# RF_circuit.net
KiCad netlist of a schematic drawn in Altium Designer
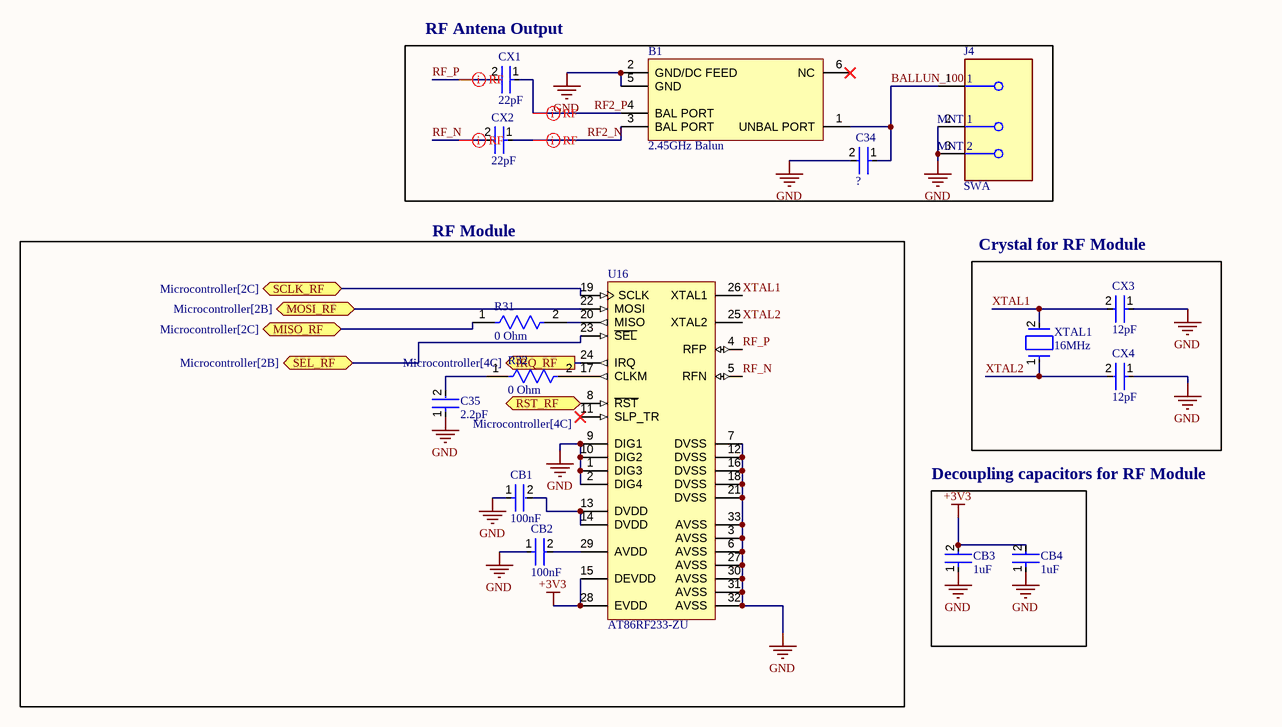
[diagram p0: RF_circuit.SchDoc]

(export (version "E")
  (design (tool "Eeschema 10.0.6"))
  (components
    (comp (ref "B1")
      (value "2.45GHz Balun")
      (footprint "WE-BAL_0805")
      (description "748421245 100O Surface Mount Chip Balun")
      (libsource (lib "Altium Content Vault") (part "WE-BAL_0805"))
    )
    (comp (ref "C34")
      (value "?")
      (footprint "FP-CC0805-0_85-MFG")
      (description "CAP CER 0.1UF 50V X7R 0805")
      (fields (field (name "TOLERANCE") "0.1") (field (name "MANUFACTURER PART NUMBER") "CC0805KRX7R9BB104"))
      (libsource (lib "Altium Content Vault") (part "11868f565c42a9108669ba33697ecf6"))
    )
    (comp (ref "C35")
      (value "2.2pF")
      (footprint "FP-CC0805-0_85-MFG")
      (description "CAP CER 0.1UF 50V X7R 0805")
      (fields (field (name "TOLERANCE") "0.1") (field (name "MANUFACTURER PART NUMBER") "CC0805KRX7R9BB104"))
      (libsource (lib "Altium Content Vault") (part "11868f565c42a9108669ba33697ecf6"))
    )
    (comp (ref "CB1")
      (value "100nF")
      (footprint "FP-CC0805-0_85-MFG")
      (description "CAP CER 0.1UF 50V X7R 0805")
      (fields (field (name "TOLERANCE") "0.1") (field (name "MANUFACTURER PART NUMBER") "CC0805KRX7R9BB104"))
      (libsource (lib "Altium Content Vault") (part "11868f565c42a9108669ba33697ecf6"))
    )
    (comp (ref "CB2")
      (value "100nF")
      (footprint "FP-CC0805-0_85-MFG")
      (description "CAP CER 0.1UF 50V X7R 0805")
      (fields (field (name "TOLERANCE") "0.1") (field (name "MANUFACTURER PART NUMBER") "CC0805KRX7R9BB104"))
      (libsource (lib "Altium Content Vault") (part "11868f565c42a9108669ba33697ecf6"))
    )
    (comp (ref "CB3")
      (value "1uF")
      (footprint "FP-CC0805-0_85-MFG")
      (description "CAP CER 0.1UF 50V X7R 0805")
      (fields (field (name "TOLERANCE") "0.1") (field (name "MANUFACTURER PART NUMBER") "CC0805KRX7R9BB104"))
      (libsource (lib "Altium Content Vault") (part "11868f565c42a9108669ba33697ecf6"))
    )
    (comp (ref "CB4")
      (value "1uF")
      (footprint "FP-CC0805-0_85-MFG")
      (description "CAP CER 0.1UF 50V X7R 0805")
      (fields (field (name "TOLERANCE") "0.1") (field (name "MANUFACTURER PART NUMBER") "CC0805KRX7R9BB104"))
      (libsource (lib "Altium Content Vault") (part "11868f565c42a9108669ba33697ecf6"))
    )
    (comp (ref "CX1")
      (value "22pF")
      (footprint "FP-CC0805-0_85-MFG")
      (description "CAP CER 0.1UF 50V X7R 0805")
      (fields (field (name "TOLERANCE") "0.1") (field (name "MANUFACTURER PART NUMBER") "CC0805KRX7R9BB104"))
      (libsource (lib "Altium Content Vault") (part "11868f565c42a9108669ba33697ecf6"))
    )
    (comp (ref "CX2")
      (value "22pF")
      (footprint "FP-CC0805-0_85-MFG")
      (description "CAP CER 0.1UF 50V X7R 0805")
      (fields (field (name "TOLERANCE") "0.1") (field (name "MANUFACTURER PART NUMBER") "CC0805KRX7R9BB104"))
      (libsource (lib "Altium Content Vault") (part "11868f565c42a9108669ba33697ecf6"))
    )
    (comp (ref "CX3")
      (value "12pF")
      (footprint "FP-CC0805-0_85-MFG")
      (description "CAP CER 0.1UF 50V X7R 0805")
      (fields (field (name "TOLERANCE") "0.1") (field (name "MANUFACTURER PART NUMBER") "CC0805KRX7R9BB104"))
      (libsource (lib "Altium Content Vault") (part "11868f565c42a9108669ba33697ecf6"))
    )
    (comp (ref "CX4")
      (value "12pF")
      (footprint "FP-CC0805-0_85-MFG")
      (description "CAP CER 0.1UF 50V X7R 0805")
      (fields (field (name "TOLERANCE") "0.1") (field (name "MANUFACTURER PART NUMBER") "CC0805KRX7R9BB104"))
      (libsource (lib "Altium Content Vault") (part "11868f565c42a9108669ba33697ecf6"))
    )
    (comp (ref "J4")
      (value "SWA")
      (footprint "FP-142-0701-801-MFG")
      (libsource (lib "Altium Content Vault") (part "89929399afe843c8b6880c6cbd0f99a"))
    )
    (comp (ref "R31")
      (value "0 Ohm")
      (footprint "FP-RMCF0805-MFG")
      (description "RES 0 OHM JUMPER 1/8W 0805")
      (libsource (lib "Altium Content Vault") (part "1029c3af85768c4190bb7ad29bc67b5"))
    )
    (comp (ref "R32")
      (value "0 Ohm")
      (footprint "FP-RMCF0805-MFG")
      (description "RES 0 OHM JUMPER 1/8W 0805")
      (libsource (lib "Altium Content Vault") (part "1029c3af85768c4190bb7ad29bc67b5"))
    )
    (comp (ref "U16")
      (value "AT86RF233-ZU")
      (footprint "32QN2_M")
      (fields (field (name "MANUFACTURER") "Atmel"))
      (libsource (lib "Altium Content Vault") (part "ATML-AT86RF233-QN-32"))
    )
    (comp (ref "XTAL1")
      (value "16MHz")
      (footprint "FP-ABLS-MFG")
      (description "CRYSTAL 16.0000MHZ 18PF SMD")
      (fields
        (field (name "TOLERANCE") "30ppm")
        (field (name "MANUFACTURER PART NUMBER") "ABLS-16.000MHZ-K4T")
      )
      (libsource (lib "Altium Content Vault") (part "c23a69dc6c9e2f18f2079038eb95dd1"))
    )
  )
  (nets
    (net (code "1") (name "+3V3") (class "Default")
      (node (ref "CB3") (pin "2") (pinfunction "2_2") (pintype "passive"))
      (node (ref "CB4") (pin "2") (pinfunction "2_2") (pintype "passive"))
      (node (ref "U16") (pin "15") (pinfunction "DEVDD_15") (pintype "power_in"))
      (node (ref "U16") (pin "28") (pinfunction "EVDD_28") (pintype "power_in"))
    )
    (net (code "2") (name "/BALLUN_100") (class "Default")
      (node (ref "B1") (pin "1") (pinfunction "UNBAL_PORT_1") (pintype "passive"))
      (node (ref "C34") (pin "1") (pinfunction "1_1") (pintype "passive"))
      (node (ref "J4") (pin "1") (pinfunction "1_1") (pintype "passive"))
    )
    (net (code "3") (name "/IRQ_RF") (class "Default")
      (node (ref "U16") (pin "24") (pinfunction "IRQ_24") (pintype "output"))
    )
    (net (code "4") (name "/MISO_RF") (class "Default")
      (node (ref "R31") (pin "1") (pinfunction "1_1") (pintype "passive"))
    )
    (net (code "5") (name "/MOSI_RF") (class "Default")
      (node (ref "U16") (pin "22") (pinfunction "MOSI_22") (pintype "input"))
    )
    (net (code "6") (name "/RF2_N") (class "Default")
      (node (ref "B1") (pin "3") (pinfunction "BAL_PORT_3") (pintype "passive"))
      (node (ref "CX2") (pin "1") (pinfunction "1_1") (pintype "passive"))
    )
    (net (code "7") (name "/RF2_P") (class "Default")
      (node (ref "B1") (pin "4") (pinfunction "BAL_PORT_4") (pintype "passive"))
      (node (ref "CX1") (pin "1") (pinfunction "1_1") (pintype "passive"))
    )
    (net (code "8") (name "/RF_N") (class "Default")
      (node (ref "CX2") (pin "2") (pinfunction "2_2") (pintype "passive"))
      (node (ref "U16") (pin "5") (pinfunction "RFN_5") (pintype "bidirectional"))
    )
    (net (code "9") (name "/RF_P") (class "Default")
      (node (ref "CX1") (pin "2") (pinfunction "2_2") (pintype "passive"))
      (node (ref "U16") (pin "4") (pinfunction "RFP_4") (pintype "bidirectional"))
    )
    (net (code "10") (name "/RST_RF") (class "Default")
      (node (ref "U16") (pin "8") (pinfunction "~{RST}_8") (pintype "input"))
    )
    (net (code "11") (name "/SCLK_RF") (class "Default")
      (node (ref "U16") (pin "19") (pinfunction "SCLK_19") (pintype "input"))
    )
    (net (code "12") (name "/SEL_RF") (class "Default")
      (node (ref "U16") (pin "23") (pinfunction "~{SEL}_23") (pintype "input"))
    )
    (net (code "13") (name "/XTAL1") (class "Default")
      (node (ref "CX3") (pin "2") (pinfunction "2_2") (pintype "passive"))
      (node (ref "U16") (pin "26") (pinfunction "XTAL1_26") (pintype "passive"))
      (node (ref "XTAL1") (pin "2") (pinfunction "2_2") (pintype "passive"))
    )
    (net (code "14") (name "/XTAL2") (class "Default")
      (node (ref "CX4") (pin "2") (pinfunction "2_2") (pintype "passive"))
      (node (ref "U16") (pin "25") (pinfunction "XTAL2_25") (pintype "passive"))
      (node (ref "XTAL1") (pin "1") (pinfunction "1_1") (pintype "passive"))
    )
    (net (code "15") (name "GND") (class "Default")
      (node (ref "B1") (pin "2") (pinfunction "GND/DC_FEED_2") (pintype "power_in"))
      (node (ref "B1") (pin "5") (pinfunction "GND_5") (pintype "power_in"))
      (node (ref "C34") (pin "2") (pinfunction "2_2") (pintype "passive"))
      (node (ref "C35") (pin "1") (pinfunction "1_1") (pintype "passive"))
      (node (ref "CB1") (pin "1") (pinfunction "1_1") (pintype "passive"))
      (node (ref "CB2") (pin "1") (pinfunction "1_1") (pintype "passive"))
      (node (ref "CB3") (pin "1") (pinfunction "1_1") (pintype "passive"))
      (node (ref "CB4") (pin "1") (pinfunction "1_1") (pintype "passive"))
      (node (ref "CX3") (pin "1") (pinfunction "1_1") (pintype "passive"))
      (node (ref "CX4") (pin "1") (pinfunction "1_1") (pintype "passive"))
      (node (ref "J4") (pin "2") (pinfunction "MNT_1_2") (pintype "passive"))
      (node (ref "J4") (pin "3") (pinfunction "MNT_2_3") (pintype "passive"))
      (node (ref "U16") (pin "1") (pinfunction "DIG3_1") (pintype "passive"))
      (node (ref "U16") (pin "10") (pinfunction "DIG2_10") (pintype "passive"))
      (node (ref "U16") (pin "12") (pinfunction "DVSS_12") (pintype "power_in"))
      (node (ref "U16") (pin "16") (pinfunction "DVSS_16") (pintype "power_in"))
      (node (ref "U16") (pin "18") (pinfunction "DVSS_18") (pintype "power_in"))
      (node (ref "U16") (pin "2") (pinfunction "DIG4_2") (pintype "passive"))
      (node (ref "U16") (pin "21") (pinfunction "DVSS_21") (pintype "power_in"))
      (node (ref "U16") (pin "27") (pinfunction "AVSS_27") (pintype "power_in"))
      (node (ref "U16") (pin "3") (pinfunction "AVSS_3") (pintype "power_in"))
      (node (ref "U16") (pin "30") (pinfunction "AVSS_30") (pintype "power_in"))
      (node (ref "U16") (pin "31") (pinfunction "AVSS_31") (pintype "power_in"))
      (node (ref "U16") (pin "32") (pinfunction "AVSS_32") (pintype "power_in"))
      (node (ref "U16") (pin "33") (pinfunction "AVSS_33") (pintype "power_in"))
      (node (ref "U16") (pin "6") (pinfunction "AVSS_6") (pintype "power_in"))
      (node (ref "U16") (pin "7") (pinfunction "DVSS_7") (pintype "power_in"))
      (node (ref "U16") (pin "9") (pinfunction "DIG1_9") (pintype "passive"))
    )
    (net (code "16") (name "Net-(C35-Pad2)") (class "Default")
      (node (ref "C35") (pin "2") (pinfunction "2_2") (pintype "passive"))
      (node (ref "R32") (pin "1") (pinfunction "1_1") (pintype "passive"))
    )
    (net (code "17") (name "Net-(CB1-Pad2)") (class "Default")
      (node (ref "CB1") (pin "2") (pinfunction "2_2") (pintype "passive"))
      (node (ref "U16") (pin "13") (pinfunction "DVDD_13") (pintype "power_in"))
      (node (ref "U16") (pin "14") (pinfunction "DVDD_14") (pintype "power_in"))
    )
    (net (code "18") (name "Net-(U16-AVDD)") (class "Default")
      (node (ref "CB2") (pin "2") (pinfunction "2_2") (pintype "passive"))
      (node (ref "U16") (pin "29") (pinfunction "AVDD_29") (pintype "power_in"))
    )
    (net (code "19") (name "Net-(U16-CLKM)") (class "Default")
      (node (ref "R32") (pin "2") (pinfunction "2_2") (pintype "passive"))
      (node (ref "U16") (pin "17") (pinfunction "CLKM_17") (pintype "output"))
    )
    (net (code "20") (name "Net-(U16-MISO)") (class "Default")
      (node (ref "R31") (pin "2") (pinfunction "2_2") (pintype "passive"))
      (node (ref "U16") (pin "20") (pinfunction "MISO_20") (pintype "output"))
    )
    (net (code "21") (name "unconnected-(B1-NC-Pad6)") (class "Default")
      (node (ref "B1") (pin "6") (pinfunction "NC_6") (pintype "passive+no_connect"))
    )
    (net (code "22") (name "unconnected-(U16-SLP_TR-Pad11)") (class "Default")
      (node (ref "U16") (pin "11") (pinfunction "SLP_TR_11") (pintype "input+no_connect"))
    )
  )
)
